# OpenRing_DaughterBoard.net
KiCad netlist of a schematic drawn in Altium Designer
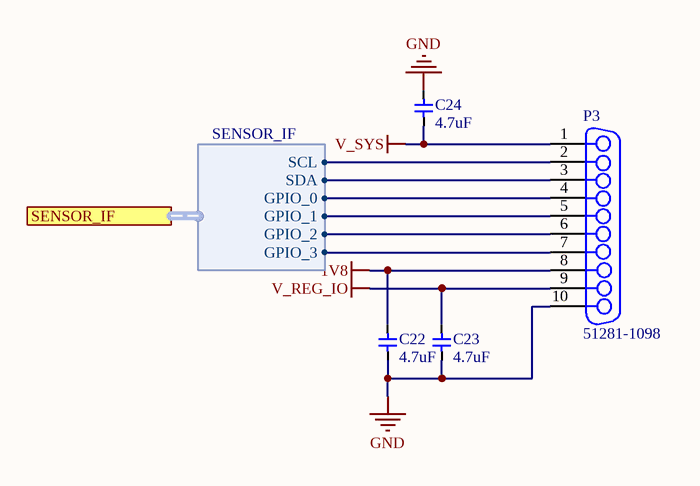
[diagram p0: OpenRing_DaughterBoard.SchDoc]

(export (version "E")
  (design (tool "Eeschema 10.0.6"))
  (components
    (comp (ref "C22")
      (value "4.7uF")
      (footprint "CAPC1005X05N")
      (description "Multilayer Ceramic Capacitor, 4.7 uF, 10 V, ± 20%, X5R, 0402 [1005 Metric]")
      (fields
        (field (name "MANUFACTURER") "Murata")
        (field (name "MANUFACTURER PART NUMBER") "GRM155R61A475MEAAD")
      )
      (libsource (lib "OpenRingComponents") (part "GRM155R61A475MEAAD"))
    )
    (comp (ref "C23")
      (value "4.7uF")
      (footprint "CAPC1005X05N")
      (description "Multilayer Ceramic Capacitor, 4.7 uF, 10 V, ± 20%, X5R, 0402 [1005 Metric]")
      (fields
        (field (name "MANUFACTURER") "Murata")
        (field (name "MANUFACTURER PART NUMBER") "GRM155R61A475MEAAD")
      )
      (libsource (lib "OpenRingComponents") (part "GRM155R61A475MEAAD"))
    )
    (comp (ref "C24")
      (value "4.7uF")
      (footprint "CAPC1005X05N")
      (description "Multilayer Ceramic Capacitor, 4.7 uF, 10 V, ± 20%, X5R, 0402 [1005 Metric]")
      (fields
        (field (name "MANUFACTURER") "Murata")
        (field (name "MANUFACTURER PART NUMBER") "GRM155R61A475MEAAD")
      )
      (libsource (lib "OpenRingComponents") (part "GRM155R61A475MEAAD"))
    )
    (comp (ref "P3")
      (value "51281-1098")
      (footprint "51281-1098")
      (description "FFC/FPC Connector, Surface Mount, Right-Angle, Non-ZIF, Dual Contact Style")
      (fields (field (name "MANUFACTURER") "Molex"))
      (libsource (lib "Connectors") (part "51281-1098"))
    )
  )
  (nets
    (net (code "2") (name "/GPIO_0") (class "Default")
      (node (ref "P3") (pin "4") (pinfunction "4_4") (pintype "passive"))
    )
    (net (code "3") (name "/GPIO_1") (class "Default")
      (node (ref "P3") (pin "5") (pinfunction "5_5") (pintype "passive"))
    )
    (net (code "4") (name "/GPIO_2") (class "Default")
      (node (ref "P3") (pin "6") (pinfunction "6_6") (pintype "passive"))
    )
    (net (code "5") (name "/GPIO_3") (class "Default")
      (node (ref "P3") (pin "7") (pinfunction "7_7") (pintype "passive"))
    )
    (net (code "6") (name "/SCL") (class "Default")
      (node (ref "P3") (pin "2") (pinfunction "2_2") (pintype "passive"))
    )
    (net (code "7") (name "/SDA") (class "Default")
      (node (ref "P3") (pin "3") (pinfunction "3_3") (pintype "passive"))
    )
    (net (code "9") (name "1V8") (class "Default")
      (node (ref "C22") (pin "2") (pinfunction "2_2") (pintype "passive"))
      (node (ref "P3") (pin "8") (pinfunction "8_8") (pintype "passive"))
    )
    (net (code "10") (name "GND") (class "Default")
      (node (ref "C22") (pin "1") (pinfunction "1_1") (pintype "passive"))
      (node (ref "C23") (pin "1") (pinfunction "1_1") (pintype "passive"))
      (node (ref "C24") (pin "2") (pinfunction "2_2") (pintype "passive"))
      (node (ref "P3") (pin "10") (pinfunction "10_10") (pintype "passive"))
    )
    (net (code "11") (name "V_REG_IO") (class "Default")
      (node (ref "C23") (pin "2") (pinfunction "2_2") (pintype "passive"))
      (node (ref "P3") (pin "9") (pinfunction "9_9") (pintype "passive"))
    )
    (net (code "12") (name "V_SYS") (class "Default")
      (node (ref "C24") (pin "1") (pinfunction "1_1") (pintype "passive"))
      (node (ref "P3") (pin "1") (pinfunction "1_1") (pintype "passive"))
    )
  )
)
